# CC3000Module.net
KiCad netlist of a schematic drawn in Altium Designer
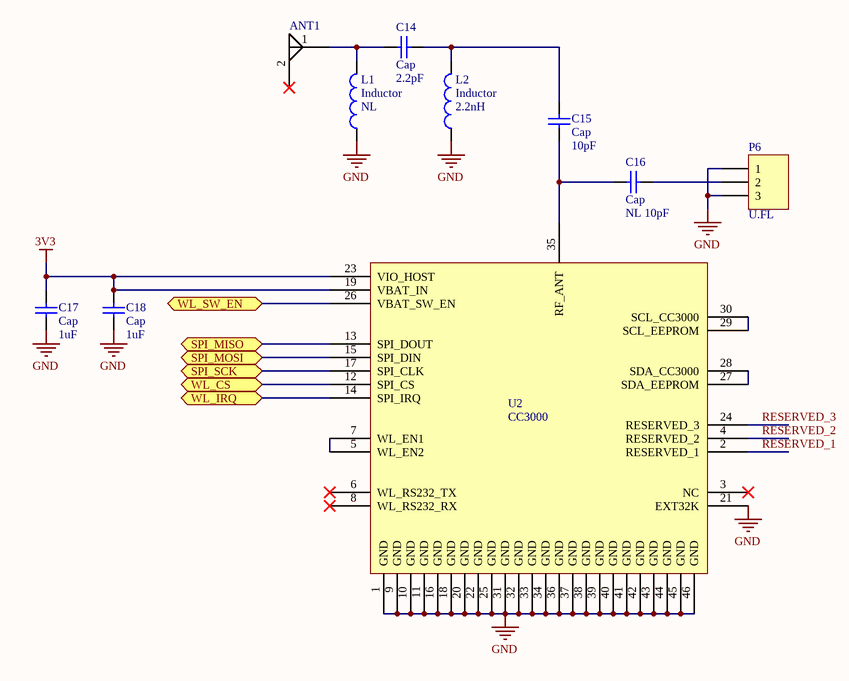
[diagram p0: CC3000Module.SchDoc]

(export (version "E")
  (design (tool "Eeschema 10.0.6"))
  (components
    (comp (ref "ANT1")
      (value "ANT-SMT-2")
      (footprint "2500AT44M0400")
      (libsource (lib "BrewBit") (part "ANT-SMT-2"))
    )
    (comp (ref "C14")
      (value "Cap")
      (footprint "0402")
      (description "Capacitor")
      (fields (field (name "ALTIUM_VALUE") "2.2pF"))
      (libsource (lib "Miscellaneous Devices") (part "Cap"))
    )
    (comp (ref "C15")
      (value "Cap")
      (footprint "0402")
      (description "Capacitor")
      (fields (field (name "ALTIUM_VALUE") "10pF"))
      (libsource (lib "Miscellaneous Devices") (part "Cap"))
    )
    (comp (ref "C16")
      (value "Cap")
      (footprint "0402")
      (description "Capacitor")
      (fields (field (name "ALTIUM_VALUE") "NL 10pF"))
      (libsource (lib "Miscellaneous Devices") (part "Cap"))
    )
    (comp (ref "C17")
      (value "Cap")
      (footprint "0402")
      (description "Capacitor")
      (fields (field (name "ALTIUM_VALUE") "1uF"))
      (libsource (lib "Miscellaneous Devices") (part "Cap"))
    )
    (comp (ref "C18")
      (value "Cap")
      (footprint "0402")
      (description "Capacitor")
      (fields (field (name "ALTIUM_VALUE") "1uF"))
      (libsource (lib "Miscellaneous Devices") (part "Cap"))
    )
    (comp (ref "L1")
      (value "Inductor")
      (footprint "0402")
      (fields (field (name "ALTIUM_VALUE") "NL"))
      (libsource (lib "Miscellaneous Devices") (part "Inductor"))
    )
    (comp (ref "L2")
      (value "Inductor")
      (footprint "0402")
      (fields (field (name "ALTIUM_VALUE") "2.2nH"))
      (libsource (lib "Miscellaneous Devices") (part "Inductor"))
    )
    (comp (ref "P6")
      (value "U.FL")
      (footprint "U.FL-R-SMT-1")
      (description "Header, 3-Pin")
      (libsource (lib "Miscellaneous Connectors") (part "Header 3"))
    )
    (comp (ref "U2")
      (value "CC3000")
      (footprint "CC3000")
      (description "CC3000 WLAN Module")
      (libsource (lib "BrewBit") (part "CC3000"))
    )
  )
  (nets
    (net (code "1") (name "/RESERVED_1") (class "Default")
      (node (ref "U2") (pin "2") (pinfunction "RESERVED_1_2") (pintype "passive"))
    )
    (net (code "2") (name "/RESERVED_2") (class "Default")
      (node (ref "U2") (pin "4") (pinfunction "RESERVED_2_4") (pintype "passive"))
    )
    (net (code "3") (name "/RESERVED_3") (class "Default")
      (node (ref "U2") (pin "24") (pinfunction "RESERVED_3_24") (pintype "passive"))
    )
    (net (code "4") (name "/SPI_MISO") (class "Default")
      (node (ref "U2") (pin "13") (pinfunction "SPI_DOUT_13") (pintype "passive"))
    )
    (net (code "5") (name "/SPI_MOSI") (class "Default")
      (node (ref "U2") (pin "15") (pinfunction "SPI_DIN_15") (pintype "passive"))
    )
    (net (code "6") (name "/SPI_SCK") (class "Default")
      (node (ref "U2") (pin "17") (pinfunction "SPI_CLK_17") (pintype "passive"))
    )
    (net (code "7") (name "/WL_CS") (class "Default")
      (node (ref "U2") (pin "12") (pinfunction "SPI_CS_12") (pintype "passive"))
    )
    (net (code "8") (name "/WL_IRQ") (class "Default")
      (node (ref "U2") (pin "14") (pinfunction "SPI_IRQ_14") (pintype "passive"))
    )
    (net (code "9") (name "/WL_SW_EN") (class "Default")
      (node (ref "U2") (pin "26") (pinfunction "VBAT_SW_EN_26") (pintype "passive"))
    )
    (net (code "10") (name "3V3") (class "Default")
      (node (ref "C17") (pin "2") (pinfunction "2_2") (pintype "passive"))
      (node (ref "C18") (pin "2") (pinfunction "2_2") (pintype "passive"))
      (node (ref "U2") (pin "19") (pinfunction "VBAT_IN_19") (pintype "passive"))
      (node (ref "U2") (pin "23") (pinfunction "VIO_HOST_23") (pintype "passive"))
    )
    (net (code "11") (name "GND") (class "Default")
      (node (ref "C17") (pin "1") (pinfunction "1_1") (pintype "passive"))
      (node (ref "C18") (pin "1") (pinfunction "1_1") (pintype "passive"))
      (node (ref "L1") (pin "1") (pinfunction "1_1") (pintype "passive"))
      (node (ref "L2") (pin "1") (pinfunction "1_1") (pintype "passive"))
      (node (ref "P6") (pin "1") (pinfunction "1_1") (pintype "passive"))
      (node (ref "P6") (pin "3") (pinfunction "3_3") (pintype "passive"))
      (node (ref "U2") (pin "1") (pinfunction "GND_1") (pintype "passive"))
      (node (ref "U2") (pin "10") (pinfunction "GND_10") (pintype "passive"))
      (node (ref "U2") (pin "11") (pinfunction "GND_11") (pintype "passive"))
      (node (ref "U2") (pin "16") (pinfunction "GND_16") (pintype "passive"))
      (node (ref "U2") (pin "18") (pinfunction "GND_18") (pintype "passive"))
      (node (ref "U2") (pin "20") (pinfunction "GND_20") (pintype "passive"))
      (node (ref "U2") (pin "21") (pinfunction "EXT32K_21") (pintype "passive"))
      (node (ref "U2") (pin "22") (pinfunction "GND_22") (pintype "passive"))
      (node (ref "U2") (pin "25") (pinfunction "GND_25") (pintype "passive"))
      (node (ref "U2") (pin "31") (pinfunction "GND_31") (pintype "passive"))
      (node (ref "U2") (pin "32") (pinfunction "GND_32") (pintype "passive"))
      (node (ref "U2") (pin "33") (pinfunction "GND_33") (pintype "passive"))
      (node (ref "U2") (pin "34") (pinfunction "GND_34") (pintype "passive"))
      (node (ref "U2") (pin "36") (pinfunction "GND_36") (pintype "passive"))
      (node (ref "U2") (pin "37") (pinfunction "GND_37") (pintype "passive"))
      (node (ref "U2") (pin "38") (pinfunction "GND_38") (pintype "passive"))
      (node (ref "U2") (pin "39") (pinfunction "GND_39") (pintype "passive"))
      (node (ref "U2") (pin "40") (pinfunction "GND_40") (pintype "passive"))
      (node (ref "U2") (pin "41") (pinfunction "GND_41") (pintype "passive"))
      (node (ref "U2") (pin "42") (pinfunction "GND_42") (pintype "passive"))
      (node (ref "U2") (pin "43") (pinfunction "GND_43") (pintype "passive"))
      (node (ref "U2") (pin "44") (pinfunction "GND_44") (pintype "passive"))
      (node (ref "U2") (pin "45") (pinfunction "GND_45") (pintype "passive"))
      (node (ref "U2") (pin "46") (pinfunction "GND_46") (pintype "passive"))
      (node (ref "U2") (pin "9") (pinfunction "GND_9") (pintype "passive"))
    )
    (net (code "12") (name "Net-(ANT1-Pad1)") (class "Default")
      (node (ref "ANT1") (pin "1") (pintype "passive"))
      (node (ref "C14") (pin "1") (pinfunction "1_1") (pintype "passive"))
      (node (ref "L1") (pin "2") (pinfunction "2_2") (pintype "passive"))
    )
    (net (code "13") (name "Net-(C14-Pad2)") (class "Default")
      (node (ref "C14") (pin "2") (pinfunction "2_2") (pintype "passive"))
      (node (ref "C15") (pin "2") (pinfunction "2_2") (pintype "passive"))
      (node (ref "L2") (pin "2") (pinfunction "2_2") (pintype "passive"))
    )
    (net (code "14") (name "Net-(C16-Pad1)") (class "Default")
      (node (ref "C16") (pin "1") (pinfunction "1_1") (pintype "passive"))
      (node (ref "P6") (pin "2") (pinfunction "2_2") (pintype "passive"))
    )
    (net (code "15") (name "Net-(U2-RF_ANT)") (class "Default")
      (node (ref "C15") (pin "1") (pinfunction "1_1") (pintype "passive"))
      (node (ref "C16") (pin "2") (pinfunction "2_2") (pintype "passive"))
      (node (ref "U2") (pin "35") (pinfunction "RF_ANT_35") (pintype "passive"))
    )
    (net (code "16") (name "Net-(U2-SCL_CC3000)") (class "Default")
      (node (ref "U2") (pin "29") (pinfunction "SCL_EEPROM_29") (pintype "passive"))
      (node (ref "U2") (pin "30") (pinfunction "SCL_CC3000_30") (pintype "passive"))
    )
    (net (code "17") (name "Net-(U2-SDA_CC3000)") (class "Default")
      (node (ref "U2") (pin "27") (pinfunction "SDA_EEPROM_27") (pintype "passive"))
      (node (ref "U2") (pin "28") (pinfunction "SDA_CC3000_28") (pintype "passive"))
    )
    (net (code "18") (name "Net-(U2-WL_EN1)") (class "Default")
      (node (ref "U2") (pin "5") (pinfunction "WL_EN2_5") (pintype "passive"))
      (node (ref "U2") (pin "7") (pinfunction "WL_EN1_7") (pintype "passive"))
    )
    (net (code "19") (name "unconnected-(ANT1-Pad2)") (class "Default")
      (node (ref "ANT1") (pin "2") (pintype "passive+no_connect"))
    )
    (net (code "20") (name "unconnected-(U2-NC-Pad3)") (class "Default")
      (node (ref "U2") (pin "3") (pinfunction "NC_3") (pintype "passive+no_connect"))
    )
    (net (code "21") (name "unconnected-(U2-WL_RS232_RX-Pad8)") (class "Default")
      (node (ref "U2") (pin "8") (pinfunction "WL_RS232_RX_8") (pintype "passive+no_connect"))
    )
    (net (code "22") (name "unconnected-(U2-WL_RS232_TX-Pad6)") (class "Default")
      (node (ref "U2") (pin "6") (pinfunction "WL_RS232_TX_6") (pintype "passive+no_connect"))
    )
  )
)
